# Control_and_Gauge.net
KiCad netlist of a schematic drawn in Altium Designer
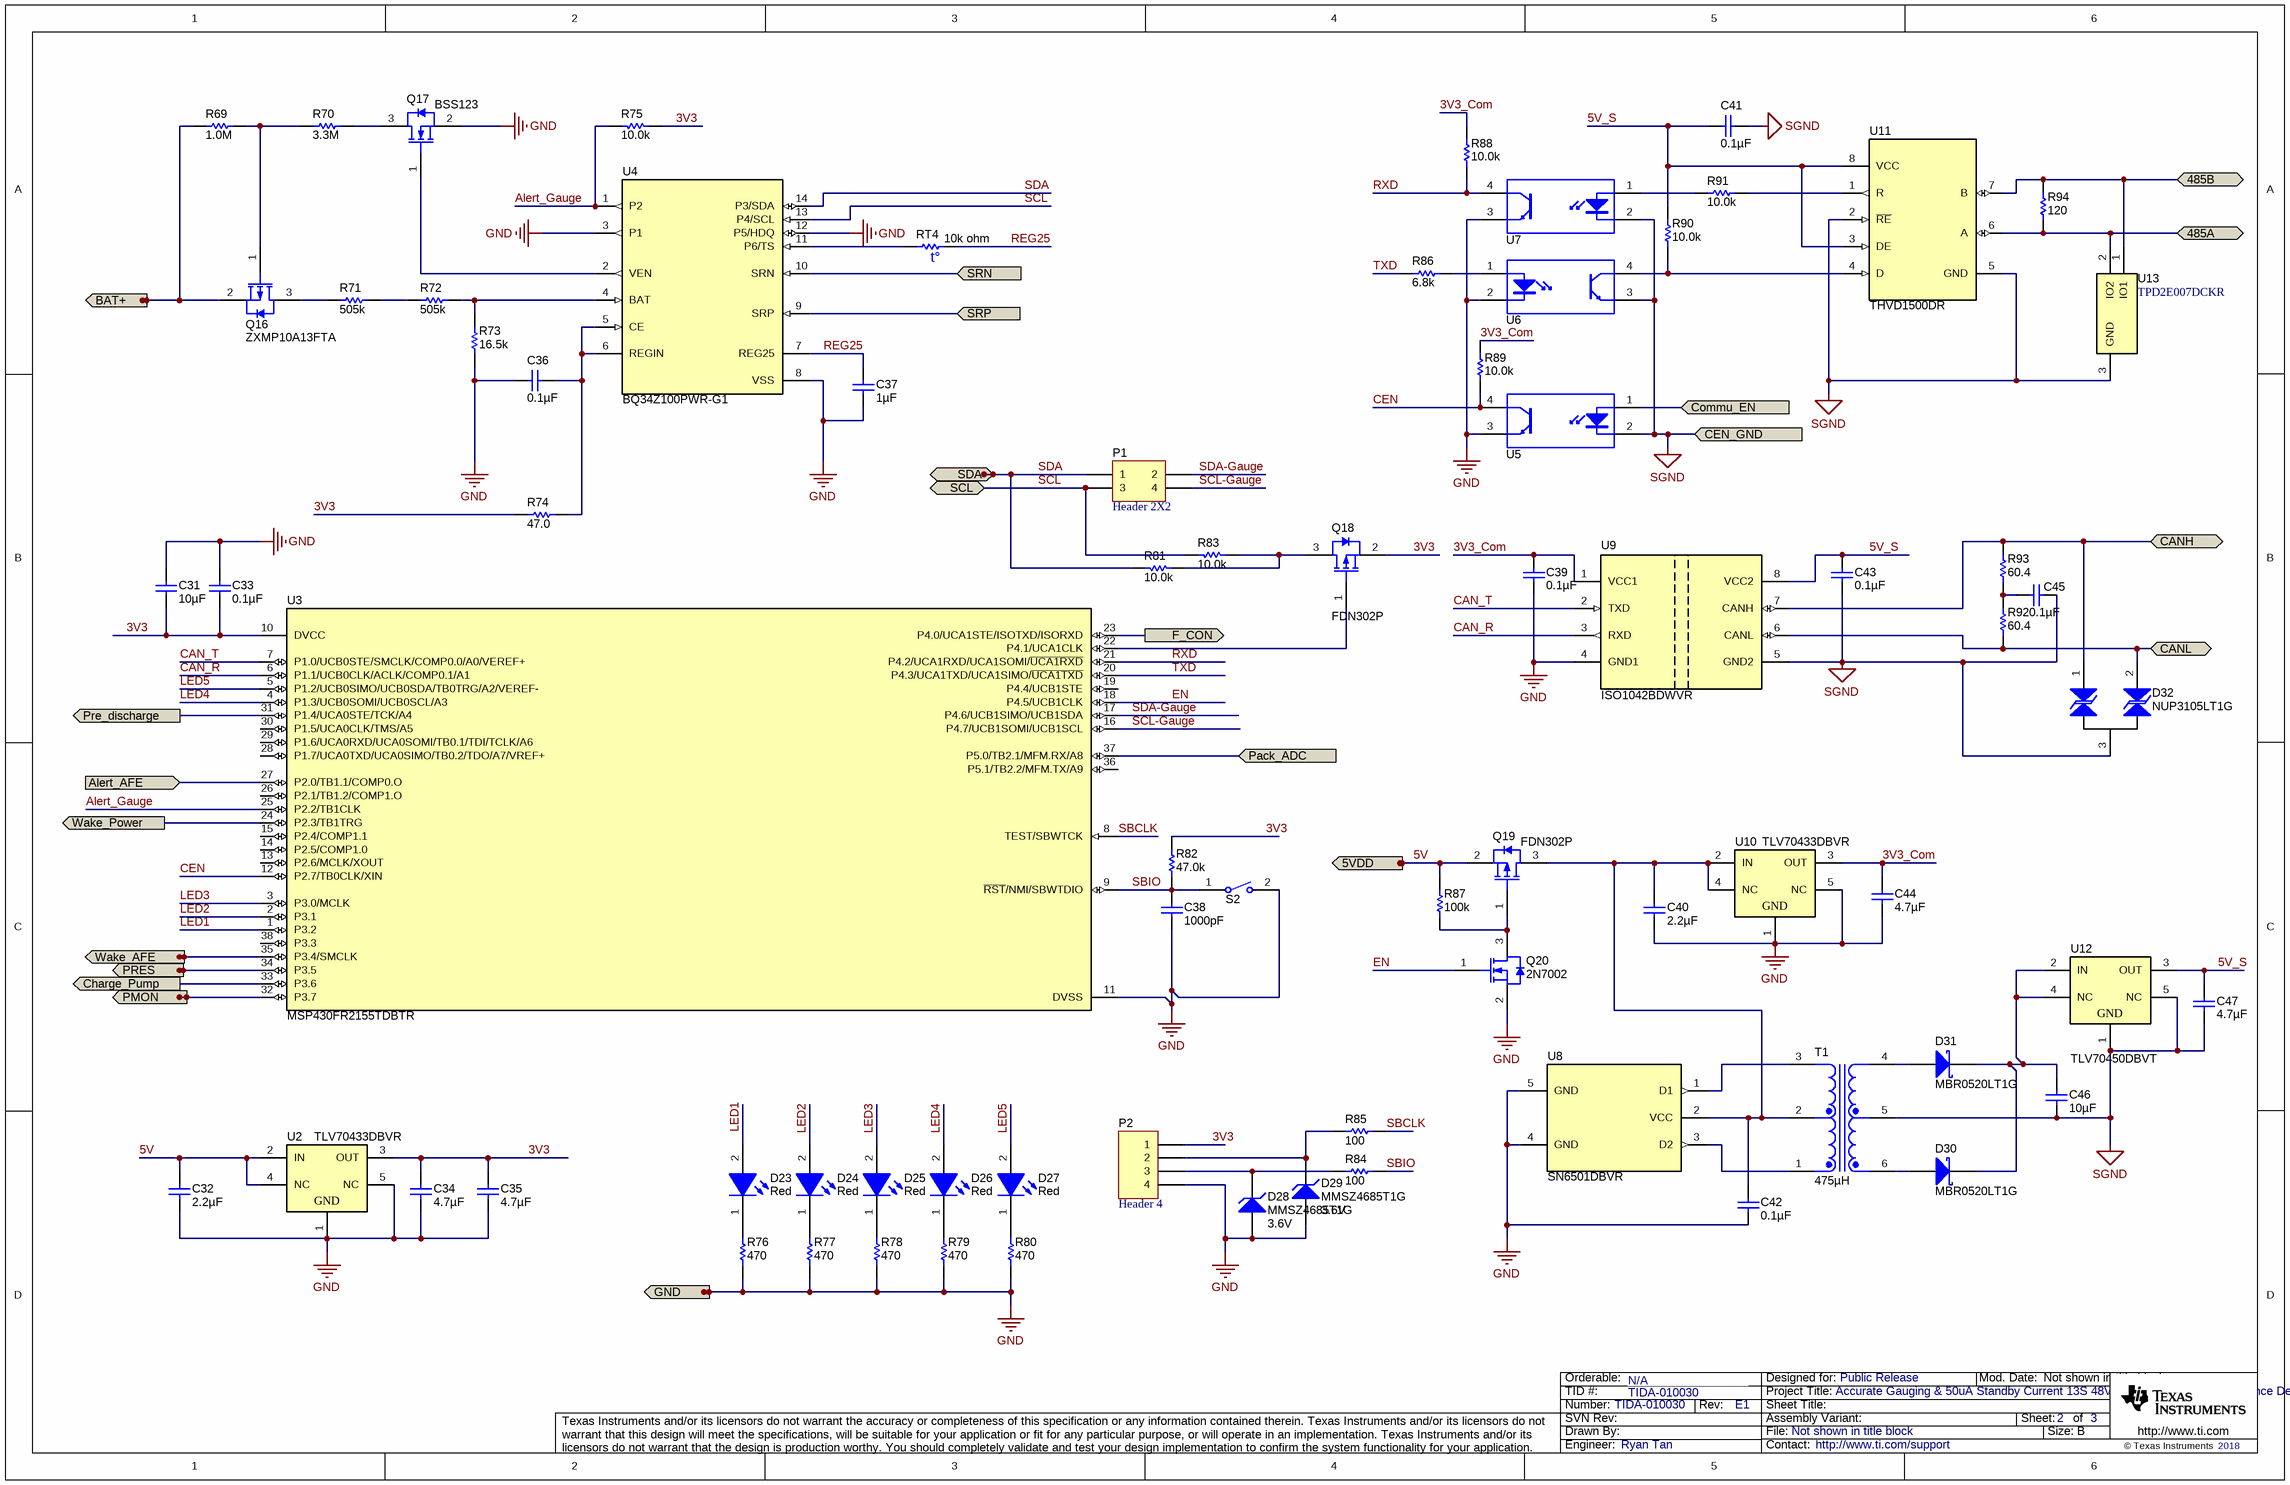
[diagram p0: Control and Gauge.SchDoc]

(export (version "E")
  (design (tool "Eeschema 10.0.6"))
  (components
    (comp (ref "C31")
      (value "CL21B106KOQNNNE")
      (footprint "0805_HV")
      (description "CAP, CERM, 10 µF, 16 V,+/- 10%, X7R, 0805")
      (fields
        (field (name "VALUEDISPLAYED") "10µF")
        (field (name "MANUFACTURER") "Samsung Electro-Mechanics")
        (field (name "PUBLISHER") "Texas Instruments")
      )
      (libsource (lib "Capacitor_Ceramic") (part "CL21B106KOQNNNE"))
    )
    (comp (ref "C32")
      (value "GRM188R71A225KE15D")
      (footprint "0603")
      (description "CAP, CERM, 2.2 µF, 10 V,+/- 10%, X7R, 0603")
      (fields
        (field (name "VALUEDISPLAYED") "2.2µF")
        (field (name "MANUFACTURER") "MuRata")
        (field (name "PUBLISHER") "Texas Instruments")
      )
      (libsource (lib "Capacitor_Ceramic") (part "GRM188R71A225KE15D"))
    )
    (comp (ref "C33")
      (value "GRM188R71C104KA01D")
      (footprint "0603")
      (description "CAP, CERM, 0.1 µF, 16 V,+/- 10%, X7R, 0603")
      (fields
        (field (name "VALUEDISPLAYED") "0.1µF")
        (field (name "MANUFACTURER") "MuRata")
        (field (name "PUBLISHER") "Texas Instruments")
      )
      (libsource (lib "Capacitor_Ceramic") (part "GRM188R71C104KA01D"))
    )
    (comp (ref "C34")
      (value "GRM188R61C475KAAJ")
      (footprint "0603")
      (description "CAP, CERM, 4.7 µF, 16 V,+/- 10%, X5R, 0603")
      (fields
        (field (name "VALUEDISPLAYED") "4.7µF")
        (field (name "MANUFACTURER") "MuRata")
        (field (name "PUBLISHER") "Texas Instruments")
      )
      (libsource (lib "Capacitor_Ceramic") (part "GRM188R61C475KAAJ"))
    )
    (comp (ref "C35")
      (value "GRM188R61C475KAAJ")
      (footprint "0603")
      (description "CAP, CERM, 4.7 µF, 16 V,+/- 10%, X5R, 0603")
      (fields
        (field (name "VALUEDISPLAYED") "4.7µF")
        (field (name "MANUFACTURER") "MuRata")
        (field (name "PUBLISHER") "Texas Instruments")
      )
      (libsource (lib "Capacitor_Ceramic") (part "GRM188R61C475KAAJ"))
    )
    (comp (ref "C36")
      (value "GRM188R71H104KA93D")
      (footprint "0603")
      (description "CAP, CERM, 0.1 µF, 50 V,+/- 10%, X7R, 0603")
      (fields
        (field (name "VALUEDISPLAYED") "0.1µF")
        (field (name "MANUFACTURER") "MuRata")
        (field (name "PUBLISHER") "Texas Instruments")
      )
      (libsource (lib "Capacitor_Ceramic") (part "GRM188R71H104KA93D"))
    )
    (comp (ref "C37")
      (value "GRM188R71C105KE15D")
      (footprint "0603")
      (description "CAP, CERM, 1 µF, 16 V,+/- 10%, X7R, 0603")
      (fields
        (field (name "VALUEDISPLAYED") "1µF")
        (field (name "MANUFACTURER") "MuRata")
        (field (name "PUBLISHER") "Texas Instruments")
      )
      (libsource (lib "Capacitor_Ceramic") (part "GRM188R71C105KE15D"))
    )
    (comp (ref "C38")
      (value "GRM1885C1H102JA01D")
      (footprint "0603S")
      (description "CAP, CERM, 1000 pF, 50 V,+/- 5%, C0G/NP0, 0603")
      (fields
        (field (name "VALUEDISPLAYED") "1000pF")
        (field (name "MANUFACTURER") "MuRata")
        (field (name "PUBLISHER") "Texas Instruments")
      )
      (libsource (lib "Capacitor_Ceramic") (part "GRM1885C1H102JA01D"))
    )
    (comp (ref "C39")
      (value "GRM188R71C104KA01D")
      (footprint "0603")
      (description "CAP, CERM, 0.1 µF, 16 V,+/- 10%, X7R, 0603")
      (fields
        (field (name "VALUEDISPLAYED") "0.1µF")
        (field (name "MANUFACTURER") "MuRata")
        (field (name "PUBLISHER") "Texas Instruments")
      )
      (libsource (lib "Capacitor_Ceramic") (part "GRM188R71C104KA01D"))
    )
    (comp (ref "C40")
      (value "GRM188R71A225KE15D")
      (footprint "0603")
      (description "CAP, CERM, 2.2 µF, 10 V,+/- 10%, X7R, 0603")
      (fields
        (field (name "VALUEDISPLAYED") "2.2µF")
        (field (name "MANUFACTURER") "MuRata")
        (field (name "PUBLISHER") "Texas Instruments")
      )
      (libsource (lib "Capacitor_Ceramic") (part "GRM188R71A225KE15D"))
    )
    (comp (ref "C41")
      (value "GRM188R71H104KA93D")
      (footprint "0603")
      (description "CAP, CERM, 0.1 µF, 50 V,+/- 10%, X7R, 0603")
      (fields
        (field (name "VALUEDISPLAYED") "0.1µF")
        (field (name "MANUFACTURER") "MuRata")
        (field (name "PUBLISHER") "Texas Instruments")
      )
      (libsource (lib "Capacitor_Ceramic") (part "GRM188R71H104KA93D"))
    )
    (comp (ref "C42")
      (value "GRM188R71C104KA01D")
      (footprint "0603")
      (description "CAP, CERM, 0.1 µF, 16 V,+/- 10%, X7R, 0603")
      (fields
        (field (name "VALUEDISPLAYED") "0.1µF")
        (field (name "MANUFACTURER") "MuRata")
        (field (name "PUBLISHER") "Texas Instruments")
      )
      (libsource (lib "Capacitor_Ceramic") (part "GRM188R71C104KA01D"))
    )
    (comp (ref "C43")
      (value "GRM188R71H104KA93D")
      (footprint "0603")
      (description "CAP, CERM, 0.1 µF, 50 V,+/- 10%, X7R, 0603")
      (fields
        (field (name "VALUEDISPLAYED") "0.1µF")
        (field (name "MANUFACTURER") "MuRata")
        (field (name "PUBLISHER") "Texas Instruments")
      )
      (libsource (lib "Capacitor_Ceramic") (part "GRM188R71H104KA93D"))
    )
    (comp (ref "C44")
      (value "GRM188R61C475KAAJ")
      (footprint "0603")
      (description "CAP, CERM, 4.7 µF, 16 V,+/- 10%, X5R, 0603")
      (fields
        (field (name "VALUEDISPLAYED") "4.7µF")
        (field (name "MANUFACTURER") "MuRata")
        (field (name "PUBLISHER") "Texas Instruments")
      )
      (libsource (lib "Capacitor_Ceramic") (part "GRM188R61C475KAAJ"))
    )
    (comp (ref "C45")
      (value "GRM188R71H104KA93D")
      (footprint "0603S")
      (description "CAP, CERM, 0.1 µF, 50 V,+/- 10%, X7R, 0603")
      (fields
        (field (name "VALUEDISPLAYED") "0.1µF")
        (field (name "MANUFACTURER") "MuRata")
        (field (name "PUBLISHER") "Texas Instruments")
      )
      (libsource (lib "Capacitor_Ceramic") (part "GRM188R71H104KA93D"))
    )
    (comp (ref "C46")
      (value "CL21B106KOQNNNE")
      (footprint "0805_HV")
      (description "CAP, CERM, 10 µF, 16 V,+/- 10%, X7R, 0805")
      (fields
        (field (name "VALUEDISPLAYED") "10µF")
        (field (name "MANUFACTURER") "Samsung Electro-Mechanics")
        (field (name "PUBLISHER") "Texas Instruments")
      )
      (libsource (lib "Capacitor_Ceramic") (part "CL21B106KOQNNNE"))
    )
    (comp (ref "C47")
      (value "GRM188R61C475KAAJ")
      (footprint "0603")
      (description "CAP, CERM, 4.7 µF, 16 V,+/- 10%, X5R, 0603")
      (fields
        (field (name "VALUEDISPLAYED") "4.7µF")
        (field (name "MANUFACTURER") "MuRata")
        (field (name "PUBLISHER") "Texas Instruments")
      )
      (libsource (lib "Capacitor_Ceramic") (part "GRM188R61C475KAAJ"))
    )
    (comp (ref "D23")
      (value "Red")
      (footprint "WL-SMCW_RED")
      (description "LED, Red, SMD")
      (fields
        (field (name "MANUFACTURER") "Wurth Elektronik")
        (field (name "PARTNUMBER") "150060RS75000")
        (field (name "PUBLISHER") "Texas Instruments")
      )
      (libsource (lib "LED") (part "150060RS75000"))
    )
    (comp (ref "D24")
      (value "Red")
      (footprint "WL-SMCW_RED")
      (description "LED, Red, SMD")
      (fields
        (field (name "MANUFACTURER") "Wurth Elektronik")
        (field (name "PARTNUMBER") "150060RS75000")
        (field (name "PUBLISHER") "Texas Instruments")
      )
      (libsource (lib "LED") (part "150060RS75000"))
    )
    (comp (ref "D25")
      (value "Red")
      (footprint "WL-SMCW_RED")
      (description "LED, Red, SMD")
      (fields
        (field (name "MANUFACTURER") "Wurth Elektronik")
        (field (name "PARTNUMBER") "150060RS75000")
        (field (name "PUBLISHER") "Texas Instruments")
      )
      (libsource (lib "LED") (part "150060RS75000"))
    )
    (comp (ref "D26")
      (value "Red")
      (footprint "WL-SMCW_RED")
      (description "LED, Red, SMD")
      (fields
        (field (name "MANUFACTURER") "Wurth Elektronik")
        (field (name "PARTNUMBER") "150060RS75000")
        (field (name "PUBLISHER") "Texas Instruments")
      )
      (libsource (lib "LED") (part "150060RS75000"))
    )
    (comp (ref "D27")
      (value "Red")
      (footprint "WL-SMCW_RED")
      (description "LED, Red, SMD")
      (fields
        (field (name "MANUFACTURER") "Wurth Elektronik")
        (field (name "PARTNUMBER") "150060RS75000")
        (field (name "PUBLISHER") "Texas Instruments")
      )
      (libsource (lib "LED") (part "150060RS75000"))
    )
    (comp (ref "D28")
      (value "MMSZ4685T1G")
      (footprint "SOD-123")
      (description "Diode, Zener, 3.6 V, 500 mW, SOD-123")
      (fields
        (field (name "ALTIUM_VALUE") "3.6V")
        (field (name "MANUFACTURER") "ON Semiconductor")
        (field (name "SYMBOLCREATOR") "a0412235")
        (field (name "PUBLISHER") "Texas Instruments")
      )
      (libsource (lib "ZenerDiodes") (part "MMSZ4685T1G"))
    )
    (comp (ref "D29")
      (value "MMSZ4685T1G")
      (footprint "SOD-123")
      (description "Diode, Zener, 3.6 V, 500 mW, SOD-123")
      (fields
        (field (name "ALTIUM_VALUE") "3.6V")
        (field (name "MANUFACTURER") "ON Semiconductor")
        (field (name "SYMBOLCREATOR") "a0412235")
        (field (name "PUBLISHER") "Texas Instruments")
      )
      (libsource (lib "ZenerDiodes") (part "MMSZ4685T1G"))
    )
    (comp (ref "D30")
      (value "MBR0520LT1G")
      (footprint "SOD-123")
      (description "Diode, Schottky, 20 V, 0.5 A, SOD-123")
      (fields (field (name "MANUFACTURER") "ON Semiconductor") (field (name "PUBLISHER") "Texas Instruments"))
      (libsource (lib "Diode") (part "MBR0520LT1G"))
    )
    (comp (ref "D31")
      (value "MBR0520LT1G")
      (footprint "SOD-123")
      (description "Diode, Schottky, 20 V, 0.5 A, SOD-123")
      (fields (field (name "MANUFACTURER") "ON Semiconductor") (field (name "PUBLISHER") "Texas Instruments"))
      (libsource (lib "Diode") (part "MBR0520LT1G"))
    )
    (comp (ref "D32")
      (value "NUP3105LT1G")
      (footprint "SOT-23")
      (description "Diode, TVS, Bi, 24 V, SOT-23")
      (fields
        (field (name "MANUFACTURER") "ON Semiconductor")
        (field (name "SYMBOLCREATOR") "a0411947")
        (field (name "PUBLISHER") "Texas Instruments")
      )
      (libsource (lib "ZenerDiodes") (part "NUP2105LT1G"))
    )
    (comp (ref "P1")
      (value "Header 2X2")
      (footprint "HDR2X2")
      (description "Header, 2-Pin, Dual row")
      (fields (field (name "PUBLISHER") "Altium Limited"))
      (libsource (lib "Miscellaneous Connectors") (part "Header 2X2"))
    )
    (comp (ref "P2")
      (value "Header 4")
      (footprint "HDR1X4")
      (description "Header, 4-Pin")
      (fields (field (name "PUBLISHER") "Altium Limited"))
      (libsource (lib "Miscellaneous Connectors") (part "Header 4"))
    )
    (comp (ref "Q16")
      (value "ZXMP10A13FTA")
      (footprint "SOT-23")
      (description "MOSFET, P-CH, -100 V, -0.6 A, SOT-23")
      (fields (field (name "MANUFACTURER") "Diodes Inc.") (field (name "PUBLISHER") "Texas Instruments"))
      (libsource (lib "FETs") (part "ZXMP10A13FTA"))
    )
    (comp (ref "Q17")
      (value "BSS123")
      (footprint "SOT-23")
      (description "MOSFET, N-CH, 100 V, 0.17 A, SOT-23")
      (fields
        (field (name "MANUFACTURER") "Fairchild Semiconductor")
        (field (name "PUBLISHER") "Texas Instruments")
      )
      (libsource (lib "FETs") (part "BSS123"))
    )
    (comp (ref "Q18")
      (value "FDN302P")
      (footprint "SOT-23")
      (description "MOSFET, P-CH, -20 V, -2.4 A, SOT-23")
      (fields
        (field (name "MANUFACTURER") "Fairchild Semiconductor")
        (field (name "PUBLISHER") "Texas Instruments")
      )
      (libsource (lib "FETs") (part "FDN302P"))
    )
    (comp (ref "Q19")
      (value "FDN302P")
      (footprint "SOT-23")
      (description "MOSFET, P-CH, -20 V, -2.4 A, SOT-23")
      (fields
        (field (name "MANUFACTURER") "Fairchild Semiconductor")
        (field (name "PUBLISHER") "Texas Instruments")
      )
      (libsource (lib "FETs") (part "FDN302P"))
    )
    (comp (ref "Q20")
      (value "2N7002")
      (footprint "SOT-23")
      (description "MOSFET, N-CH, 60 V, 115 A, SOT-23")
      (fields
        (field (name "MANUFACTURER") "Fairchild Semiconductor")
        (field (name "PUBLISHER") "Texas Instruments")
      )
      (libsource (lib "FETs") (part "2N7002"))
    )
    (comp (ref "R69")
      (value "CRCW06031M00JNEA")
      (footprint "0603")
      (description "RES, 1.0 M, 5%, 0.1 W, 0603")
      (fields
        (field (name "VALUEDISPLAYED") "1.0M")
        (field (name "MANUFACTURER") "Vishay-Dale")
        (field (name "PUBLISHER") "Texas Instruments")
      )
      (libsource (lib "Resistor_0603") (part "CRCW06031M00JNEA"))
    )
    (comp (ref "R70")
      (value "CRCW06033M30JNEA")
      (footprint "0603")
      (description "RES, 3.3 M, 5%, 0.1 W, 0603")
      (fields
        (field (name "VALUEDISPLAYED") "3.3M")
        (field (name "MANUFACTURER") "Vishay-Dale")
        (field (name "PUBLISHER") "Texas Instruments")
      )
      (libsource (lib "Resistor_0603") (part "CRCW06033M30JNEA"))
    )
    (comp (ref "R71")
      (value "RT0603BRD07505KL")
      (footprint "0603")
      (description "RES, 505 k, 0.1%, 0.1 W, 0603")
      (fields
        (field (name "VALUEDISPLAYED") "505k")
        (field (name "MANUFACTURER") "Yageo America")
        (field (name "PUBLISHER") "Texas Instruments")
      )
      (libsource (lib "Resistor_0603") (part "RT0603BRD07505KL"))
    )
    (comp (ref "R72")
      (value "RT0603BRD07505KL")
      (footprint "0603")
      (description "RES, 505 k, 0.1%, 0.1 W, 0603")
      (fields
        (field (name "VALUEDISPLAYED") "505k")
        (field (name "MANUFACTURER") "Yageo America")
        (field (name "PUBLISHER") "Texas Instruments")
      )
      (libsource (lib "Resistor_0603") (part "RT0603BRD07505KL"))
    )
    (comp (ref "R73")
      (value "RT0603BRD0716K5L")
      (footprint "0603")
      (description "RES, 16.5 k, 0.1%, 0.1 W, 0603")
      (fields
        (field (name "VALUEDISPLAYED") "16.5k")
        (field (name "MANUFACTURER") "Yageo America")
        (field (name "PUBLISHER") "Texas Instruments")
      )
      (libsource (lib "Resistor_0603") (part "RT0603BRD0716K5L"))
    )
    (comp (ref "R74")
      (value "RC0603FR-0747RL")
      (footprint "0603")
      (description "RES, 47.0, 1%, 0.1 W, 0603")
      (fields
        (field (name "VALUEDISPLAYED") "47.0")
        (field (name "MANUFACTURER") "Yageo America")
        (field (name "PUBLISHER") "Texas Instruments")
      )
      (libsource (lib "Resistor_0603") (part "RC0603FR-0747RL"))
    )
    (comp (ref "R75")
      (value "CRCW060310K0FKEA")
      (footprint "0603")
      (description "RES, 10.0 k, 1%, 0.1 W, 0603")
      (fields
        (field (name "VALUEDISPLAYED") "10.0k")
        (field (name "MANUFACTURER") "Vishay-Dale")
        (field (name "PUBLISHER") "Texas Instruments")
      )
      (libsource (lib "Resistor_0603") (part "CRCW060310K0FKEA"))
    )
    (comp (ref "R76")
      (value "RC0603FR-07470RL")
      (footprint "0603")
      (description "RES, 470, 1%, 0.1 W, 0603")
      (fields
        (field (name "VALUEDISPLAYED") "470")
        (field (name "MANUFACTURER") "Yageo America")
        (field (name "PUBLISHER") "Texas Instruments")
      )
      (libsource (lib "Resistor_0603") (part "RC0603FR-07470RL"))
    )
    (comp (ref "R77")
      (value "RC0603FR-07470RL")
      (footprint "0603")
      (description "RES, 470, 1%, 0.1 W, 0603")
      (fields
        (field (name "VALUEDISPLAYED") "470")
        (field (name "MANUFACTURER") "Yageo America")
        (field (name "PUBLISHER") "Texas Instruments")
      )
      (libsource (lib "Resistor_0603") (part "RC0603FR-07470RL"))
    )
    (comp (ref "R78")
      (value "RC0603FR-07470RL")
      (footprint "0603")
      (description "RES, 470, 1%, 0.1 W, 0603")
      (fields
        (field (name "VALUEDISPLAYED") "470")
        (field (name "MANUFACTURER") "Yageo America")
        (field (name "PUBLISHER") "Texas Instruments")
      )
      (libsource (lib "Resistor_0603") (part "RC0603FR-07470RL"))
    )
    (comp (ref "R79")
      (value "RC0603FR-07470RL")
      (footprint "0603")
      (description "RES, 470, 1%, 0.1 W, 0603")
      (fields
        (field (name "VALUEDISPLAYED") "470")
        (field (name "MANUFACTURER") "Yageo America")
        (field (name "PUBLISHER") "Texas Instruments")
      )
      (libsource (lib "Resistor_0603") (part "RC0603FR-07470RL"))
    )
    (comp (ref "R80")
      (value "RC0603FR-07470RL")
      (footprint "0603")
      (description "RES, 470, 1%, 0.1 W, 0603")
      (fields
        (field (name "VALUEDISPLAYED") "470")
        (field (name "MANUFACTURER") "Yageo America")
        (field (name "PUBLISHER") "Texas Instruments")
      )
      (libsource (lib "Resistor_0603") (part "RC0603FR-07470RL"))
    )
    (comp (ref "R81")
      (value "CRCW060310K0FKEA")
      (footprint "0603")
      (description "RES, 10.0 k, 1%, 0.1 W, 0603")
      (fields
        (field (name "VALUEDISPLAYED") "10.0k")
        (field (name "MANUFACTURER") "Vishay-Dale")
        (field (name "PUBLISHER") "Texas Instruments")
      )
      (libsource (lib "Resistor_0603") (part "CRCW060310K0FKEA"))
    )
    (comp (ref "R82")
      (value "RC0603FR-0747KL")
      (footprint "0603")
      (description "RES, 47.0 k, 1%, 0.1 W, 0603")
      (fields
        (field (name "VALUEDISPLAYED") "47.0k")
        (field (name "MANUFACTURER") "Yageo America")
        (field (name "PUBLISHER") "Texas Instruments")
      )
      (libsource (lib "Resistor_0603") (part "RC0603FR-0747KL"))
    )
    (comp (ref "R83")
      (value "CRCW060310K0FKEA")
      (footprint "0603")
      (description "RES, 10.0 k, 1%, 0.1 W, 0603")
      (fields
        (field (name "VALUEDISPLAYED") "10.0k")
        (field (name "MANUFACTURER") "Vishay-Dale")
        (field (name "PUBLISHER") "Texas Instruments")
      )
      (libsource (lib "Resistor_0603") (part "CRCW060310K0FKEA"))
    )
    (comp (ref "R84")
      (value "CRCW0603100RFKEA")
      (footprint "0603")
      (description "RES, 100, 1%, 0.1 W, 0603")
      (fields
        (field (name "VALUEDISPLAYED") "100")
        (field (name "MANUFACTURER") "Vishay-Dale")
        (field (name "PUBLISHER") "Texas Instruments")
      )
      (libsource (lib "Resistor_0603") (part "CRCW0603100RFKEA"))
    )
    (comp (ref "R85")
      (value "CRCW0603100RFKEA")
      (footprint "0603")
      (description "RES, 100, 1%, 0.1 W, 0603")
      (fields
        (field (name "VALUEDISPLAYED") "100")
        (field (name "MANUFACTURER") "Vishay-Dale")
        (field (name "PUBLISHER") "Texas Instruments")
      )
      (libsource (lib "Resistor_0603") (part "CRCW0603100RFKEA"))
    )
    (comp (ref "R86")
      (value "CRCW06036K80JNEA")
      (footprint "0603")
      (description "RES, 6.8 k, 5%, 0.1 W, 0603")
      (fields
        (field (name "VALUEDISPLAYED") "6.8k")
        (field (name "MANUFACTURER") "Vishay-Dale")
        (field (name "PUBLISHER") "Texas Instruments")
      )
      (libsource (lib "Resistor_0603") (part "CRCW06036K80JNEA"))
    )
    (comp (ref "R87")
      (value "CRCW0603100KFKEA")
      (footprint "0603")
      (description "RES, 100 k, 1%, 0.1 W, 0603")
      (fields
        (field (name "VALUEDISPLAYED") "100k")
        (field (name "MANUFACTURER") "Vishay-Dale")
        (field (name "PUBLISHER") "Texas Instruments")
      )
      (libsource (lib "Resistor_0603") (part "CRCW0603100KFKEA"))
    )
    (comp (ref "R88")
      (value "CRCW060310K0FKEA")
      (footprint "0603")
      (description "RES, 10.0 k, 1%, 0.1 W, 0603")
      (fields
        (field (name "VALUEDISPLAYED") "10.0k")
        (field (name "MANUFACTURER") "Vishay-Dale")
        (field (name "PUBLISHER") "Texas Instruments")
      )
      (libsource (lib "Resistor_0603") (part "CRCW060310K0FKEA"))
    )
    (comp (ref "R89")
      (value "CRCW060310K0FKEA")
      (footprint "0603")
      (description "RES, 10.0 k, 1%, 0.1 W, 0603")
      (fields
        (field (name "VALUEDISPLAYED") "10.0k")
        (field (name "MANUFACTURER") "Vishay-Dale")
        (field (name "PUBLISHER") "Texas Instruments")
      )
      (libsource (lib "Resistor_0603") (part "CRCW060310K0FKEA"))
    )
    (comp (ref "R90")
      (value "CRCW060310K0FKEA")
      (footprint "0603")
      (description "RES, 10.0 k, 1%, 0.1 W, 0603")
      (fields
        (field (name "VALUEDISPLAYED") "10.0k")
        (field (name "MANUFACTURER") "Vishay-Dale")
        (field (name "PUBLISHER") "Texas Instruments")
      )
      (libsource (lib "Resistor_0603") (part "CRCW060310K0FKEA"))
    )
    (comp (ref "R91")
      (value "CRCW060310K0FKEA")
      (footprint "0603S")
      (description "RES, 10.0 k, 1%, 0.1 W, 0603")
      (fields
        (field (name "VALUEDISPLAYED") "10.0k")
        (field (name "MANUFACTURER") "Vishay-Dale")
        (field (name "PUBLISHER") "Texas Instruments")
      )
      (libsource (lib "Resistor_0603") (part "CRCW060310K0FKEA"))
    )
    (comp (ref "R92")
      (value "RC0603FR-0760R4L")
      (footprint "0603S")
      (description "RES, 60.4, 1%, 0.1 W, 0603")
      (fields
        (field (name "VALUEDISPLAYED") "60.4")
        (field (name "MANUFACTURER") "Yageo America")
        (field (name "PUBLISHER") "Texas Instruments")
      )
      (libsource (lib "Resistor_0603") (part "RC0603FR-0760R4L"))
    )
    (comp (ref "R93")
      (value "RC0603FR-0760R4L")
      (footprint "0603S")
      (description "RES, 60.4, 1%, 0.1 W, 0603")
      (fields
        (field (name "VALUEDISPLAYED") "60.4")
        (field (name "MANUFACTURER") "Yageo America")
        (field (name "PUBLISHER") "Texas Instruments")
      )
      (libsource (lib "Resistor_0603") (part "RC0603FR-0760R4L"))
    )
    (comp (ref "R94")
      (value "RC0603FR-07120RL")
      (footprint "0603")
      (description "RES, 120, 1%, 0.1 W, 0603")
      (fields
        (field (name "VALUEDISPLAYED") "120")
        (field (name "MANUFACTURER") "Yageo America")
        (field (name "PUBLISHER") "Texas Instruments")
      )
      (libsource (lib "Resistor_0603") (part "RC0603FR-07120RL"))
    )
    (comp (ref "RT4")
      (value "10k ohm")
      (footprint "NTCALUG03")
      (description "Thermistor NTC, 10k ohm, 2%, NTC Thermistor, Mini Lug Sensor, Pitch 1.5mm")
      (fields
        (field (name "PARTNUMBER") "NTCALUG03A103G")
        (field (name "MANUFACTURER") "Vishay-Bccomponents")
        (field (name "PUBLISHER") "Texas Instruments")
      )
      (libsource (lib "ThermistorNTC") (part "NTCALUG03A103G"))
    )
    (comp (ref "S2")
      (value "RS-032G05A3-SM RT")
      (footprint "SW_RS-032G05A3-SM")
      (description "Switch, Tactile, SPST-NO, 0.05A, 12V, SMD")
      (fields
        (field (name "MANUFACTURER") "C&K Components")
        (field (name "SYMBOLCREATOR") "a0799628")
        (field (name "PUBLISHER") "Texas Instruments")
      )
      (libsource (lib "Switches") (part "RS-032G05A3-SM RT"))
    )
    (comp (ref "T1")
      (value "760390012")
      (footprint "Wurth_760390012")
      (description "Transformer, 475 uH, SMT")
      (fields
        (field (name "VALUEDISPLAYED") "475µH")
        (field (name "MANUFACTURER") "Wurth Elektronik")
        (field (name "SYMBOLCREATOR") "Altium")
        (field (name "PUBLISHER") "Texas Instruments")
      )
      (libsource (lib "Transformers") (part "760390012"))
    )
    (comp (ref "U2")
      (value "TLV70433DBVR")
      (footprint "DBV0005A_N")
      (fields
        (field (name "MANUFACTURER") "Texas Instruments")
        (field (name "ALTERNATE PARTNUMBER") "Equivalent")
      )
      (libsource (lib "TI Power Management Linear Regulator Single Channel LDO (0-350mA)") (part "TLV70433DBVR"))
    )
    (comp (ref "U3")
      (value "MSP430FR2155TDBTR")
      (footprint "DBT0038A_N")
      (description "24MHz 105C ULP Microcontroller With 32 KB FRAM, 4 KB SRAM, 44 IO, 12-bit ADC, DBT0038A (TSSOP-38)")
      (fields
        (field (name "PARTNUMBER") "MSP430FR2155TDBTR")
        (field (name "MANUFACTURER") "Texas Instruments")
        (field (name "ALTERNATE PARTNUMBER") "MSP430FR2155TDBT")
      )
      (libsource (lib "Altium Vault - TI") (part "MSP430FR215xTDBT"))
    )
    (comp (ref "U4")
      (value "BQ34Z100PWR-G1")
      (footprint "PW0014A_N")
      (description "Multi-Chemistry Impedance Track Standalone Fuel Gauge")
      (fields
        (field (name "ALTERNATE PARTNUMBER") "BQ34Z100PW-G1")
        (field (name "MANUFACTURER") "Texas Instruments")
        (field (name "PARTNUMBER") "BQ34Z100PWR-G1")
      )
      (libsource (lib "Altium Vault - TI") (part "BQ34Z100"))
    )
    (comp (ref "U5")
      (value "TLP293(GB-TPL,E")
      (footprint "SO4")
      (description "Optocoupler, 3.75 kV, 100-600% CTR, SMT")
      (fields (field (name "MANUFACTURER") "Toshiba") (field (name "PUBLISHER") "Texas Instruments"))
      (libsource (lib "OptoCouplers") (part "TLP293(GB-TPL,E"))
    )
    (comp (ref "U6")
      (value "TLP293(GB-TPL,E")
      (footprint "SO4")
      (description "Optocoupler, 3.75 kV, 100-600% CTR, SMT")
      (fields (field (name "MANUFACTURER") "Toshiba") (field (name "PUBLISHER") "Texas Instruments"))
      (libsource (lib "OptoCouplers") (part "TLP293(GB-TPL,E"))
    )
    (comp (ref "U7")
      (value "TLP293(GB-TPL,E")
      (footprint "SO4")
      (description "Optocoupler, 3.75 kV, 100-600% CTR, SMT")
      (fields (field (name "MANUFACTURER") "Toshiba") (field (name "PUBLISHER") "Texas Instruments"))
      (libsource (lib "OptoCouplers") (part "TLP293(GB-TPL,E"))
    )
    (comp (ref "U8")
      (value "SN6501DBVR")
      (footprint "DBV0005A_N")
      (description "Low-Noise 350 mA, 410 kHz Transformer Driver, DBV0005A (SOT-23-5)")
      (fields
        (field (name "ALTERNATE PARTNUMBER") "SN6501DBVT")
        (field (name "MANUFACTURER") "Texas Instruments")
        (field (name "PARTNUMBER") "SN6501DBVR")
        (field (name "PUBLISHER") "Texas Instruments")
      )
      (libsource (lib "Altium Vault - TI") (part "SN6501"))
    )
    (comp (ref "U9")
      (value "ISO1042BDWVR")
      (footprint "DWV0008A")
      (description "Reinforced Isolated CAN XCVRs with 70V Protection Voltage and CAN FD, DWV0008A (SOIC-8)")
      (fields
        (field (name "ALTERNATE PARTNUMBER") "ISO1042BDWV")
        (field (name "MANUFACTURER") "Texas Instruments")
        (field (name "PARTNUMBER") "ISO1042BDWVR")
      )
      (libsource (lib "Altium Vault - TI") (part "CMP-0077952-1"))
    )
    (comp (ref "U10")
      (value "TLV70433DBVR")
      (footprint "DBV0005A_N")
      (fields
        (field (name "MANUFACTURER") "Texas Instruments")
        (field (name "ALTERNATE PARTNUMBER") "Equivalent")
      )
      (libsource (lib "TI Power Management Linear Regulator Single Channel LDO (0-350mA)") (part "TLV70433DBVR"))
    )
    (comp (ref "U11")
      (value "THVD1500DR")
      (footprint "D0008A_N")
      (description "250 kbps RS-485 Transceivers With +/-12-kV IEC ESD Protection, D0008A (SOIC-8)")
      (fields
        (field (name "PARTNUMBER") "THVD1500DR")
        (field (name "MANUFACTURER") "Texas Instruments")
        (field (name "ALTERNATE PARTNUMBER") "THVD1500D")
        (field (name "PUBLISHER") "Texas Instruments")
      )
      (libsource (lib "Altium Vault - TI") (part "THVD1500"))
    )
    (comp (ref "U12")
      (value "TLV70450DBVT")
      (footprint "DBV0005A_N")
      (fields
        (field (name "MANUFACTURER") "Texas Instruments")
        (field (name "ALTERNATE PARTNUMBER") "Equivalent")
      )
      (libsource (lib "TI Power Management Linear Regulator Single Channel LDO (0-350mA)") (part "TLV70450DBVT"))
    )
    (comp (ref "U13")
      (value "TPD2E007DCKR")
      (footprint "DCK0003A_N")
      (fields
        (field (name "MANUFACTURER") "Texas Instruments")
        (field (name "ALTERNATE PARTNUMBER") "Equivalent")
      )
      (libsource (lib "TI Interface ESD EMI Protection") (part "TPD2E007DCKR"))
    )
  )
  (nets
    (net (code "1") (name "/3V3") (class "Default")
      (node (ref "C31") (pin "2") (pinfunction "2_2") (pintype "passive"))
      (node (ref "C33") (pin "2") (pinfunction "2_2") (pintype "passive"))
      (node (ref "C34") (pin "1") (pinfunction "1_1") (pintype "passive"))
      (node (ref "C35") (pin "1") (pinfunction "1_1") (pintype "passive"))
      (node (ref "P2") (pin "1") (pinfunction "1_1") (pintype "passive"))
      (node (ref "Q18") (pin "2") (pinfunction "S_2") (pintype "passive"))
      (node (ref "R74") (pin "1") (pinfunction "1_1") (pintype "passive"))
      (node (ref "R75") (pin "1") (pinfunction "1_1") (pintype "passive"))
      (node (ref "R82") (pin "2") (pinfunction "2_2") (pintype "passive"))
      (node (ref "U2") (pin "3") (pinfunction "OUT_3") (pintype "power_in"))
      (node (ref "U3") (pin "10") (pinfunction "DVCC_10") (pintype "power_in"))
    )
    (net (code "2") (name "/3V3_Com") (class "Default")
      (node (ref "C39") (pin "2") (pinfunction "2_2") (pintype "passive"))
      (node (ref "C44") (pin "1") (pinfunction "1_1") (pintype "passive"))
      (node (ref "R88") (pin "2") (pinfunction "2_2") (pintype "passive"))
      (node (ref "R89") (pin "2") (pinfunction "2_2") (pintype "passive"))
      (node (ref "U10") (pin "3") (pinfunction "OUT_3") (pintype "power_in"))
      (node (ref "U9") (pin "1") (pinfunction "VCC1_1") (pintype "power_in"))
    )
    (net (code "3") (name "/5V") (class "Default")
      (node (ref "C32") (pin "1") (pinfunction "1_1") (pintype "passive"))
      (node (ref "Q19") (pin "2") (pinfunction "S_2") (pintype "passive"))
      (node (ref "R87") (pin "1") (pinfunction "1_1") (pintype "passive"))
      (node (ref "U2") (pin "2") (pinfunction "IN_2") (pintype "power_in"))
      (node (ref "U2") (pin "4") (pinfunction "NC_4") (pintype "passive"))
    )
    (net (code "4") (name "/5V_S") (class "Default")
      (node (ref "C41") (pin "1") (pinfunction "1_1") (pintype "passive"))
      (node (ref "C43") (pin "1") (pinfunction "1_1") (pintype "passive"))
      (node (ref "C47") (pin "1") (pinfunction "1_1") (pintype "passive"))
      (node (ref "R90") (pin "2") (pinfunction "2_2") (pintype "passive"))
      (node (ref "U11") (pin "3") (pinfunction "DE_3") (pintype "input"))
      (node (ref "U11") (pin "8") (pinfunction "VCC_8") (pintype "passive"))
      (node (ref "U12") (pin "3") (pinfunction "OUT_3") (pintype "power_in"))
      (node (ref "U9") (pin "8") (pinfunction "VCC2_8") (pintype "power_in"))
    )
    (net (code "5") (name "/485A") (class "Default")
      (node (ref "R94") (pin "2") (pinfunction "2_2") (pintype "passive"))
      (node (ref "U11") (pin "6") (pinfunction "A_6") (pintype "bidirectional"))
      (node (ref "U13") (pin "2") (pinfunction "IO2_2") (pintype "passive"))
    )
    (net (code "6") (name "/485B") (class "Default")
      (node (ref "R94") (pin "1") (pinfunction "1_1") (pintype "passive"))
      (node (ref "U11") (pin "7") (pinfunction "B_7") (pintype "bidirectional"))
      (node (ref "U13") (pin "1") (pinfunction "IO1_1") (pintype "passive"))
    )
    (net (code "7") (name "/Alert_AFE") (class "Default")
      (node (ref "U3") (pin "27") (pinfunction "P2.0/TB1.1/COMP0.O_27") (pintype "bidirectional"))
    )
    (net (code "8") (name "/Alert_Gauge") (class "Default")
      (node (ref "R75") (pin "2") (pinfunction "2_2") (pintype "passive"))
      (node (ref "U3") (pin "25") (pinfunction "P2.2/TB1CLK_25") (pintype "bidirectional"))
      (node (ref "U4") (pin "1") (pinfunction "P2_1") (pintype "output"))
    )
    (net (code "9") (name "/BAT+") (class "Default")
      (node (ref "Q16") (pin "2") (pinfunction "S_2") (pintype "passive"))
      (node (ref "R69") (pin "1") (pinfunction "1_1") (pintype "passive"))
    )
    (net (code "10") (name "/CANH") (class "Default")
      (node (ref "D32") (pin "1") (pinfunction "1_1") (pintype "passive"))
      (node (ref "R93") (pin "1") (pinfunction "1_1") (pintype "passive"))
      (node (ref "U9") (pin "7") (pinfunction "CANH_7") (pintype "bidirectional"))
    )
    (net (code "11") (name "/CANL") (class "Default")
      (node (ref "D32") (pin "2") (pinfunction "2_2") (pintype "passive"))
      (node (ref "R92") (pin "2") (pinfunction "2_2") (pintype "passive"))
      (node (ref "U9") (pin "6") (pinfunction "CANL_6") (pintype "bidirectional"))
    )
    (net (code "12") (name "/CAN_R") (class "Default")
      (node (ref "U3") (pin "6") (pinfunction "P1.1/UCB0CLK/ACLK/COMP0.1/A1_6") (pintype "bidirectional"))
      (node (ref "U9") (pin "3") (pinfunction "RXD_3") (pintype "output"))
    )
    (net (code "13") (name "/CAN_T") (class "Default")
      (node (ref "U3") (pin "7") (pinfunction "P1.0/UCB0STE/SMCLK/COMP0.0/A0/VEREF+_7") (pintype "bidirectional"))
      (node (ref "U9") (pin "2") (pinfunction "TXD_2") (pintype "input"))
    )
    (net (code "14") (name "/CEN") (class "Default")
      (node (ref "R89") (pin "1") (pinfunction "1_1") (pintype "passive"))
      (node (ref "U3") (pin "12") (pinfunction "P2.7/TB0CLK/XIN_12") (pintype "bidirectional"))
      (node (ref "U5") (pin "4") (pinfunction "C_4") (pintype "passive"))
    )
    (net (code "15") (name "/Charge_Pump") (class "Default")
      (node (ref "U3") (pin "33") (pinfunction "P3.6_33") (pintype "bidirectional"))
    )
    (net (code "16") (name "/Commu_EN") (class "Default")
      (node (ref "U5") (pin "1") (pinfunction "A_1") (pintype "passive"))
    )
    (net (code "17") (name "/EN") (class "Default")
      (node (ref "Q20") (pin "1") (pinfunction "G_1") (pintype "passive"))
      (node (ref "U3") (pin "18") (pinfunction "P4.5/UCB1CLK_18") (pintype "bidirectional"))
    )
    (net (code "18") (name "/F_CON") (class "Default")
      (node (ref "U3") (pin "23") (pinfunction "P4.0/UCA1STE/ISOTXD/ISORXD_23") (pintype "bidirectional"))
    )
    (net (code "19") (name "/LED1") (class "Default")
      (node (ref "D23") (pin "2") (pinfunction "A_2") (pintype "passive"))
      (node (ref "U3") (pin "1") (pinfunction "P3.2_1") (pintype "bidirectional"))
    )
    (net (code "20") (name "/LED2") (class "Default")
      (node (ref "D24") (pin "2") (pinfunction "A_2") (pintype "passive"))
      (node (ref "U3") (pin "2") (pinfunction "P3.1_2") (pintype "bidirectional"))
    )
    (net (code "21") (name "/LED3") (class "Default")
      (node (ref "D25") (pin "2") (pinfunction "A_2") (pintype "passive"))
      (node (ref "U3") (pin "3") (pinfunction "P3.0/MCLK_3") (pintype "bidirectional"))
    )
    (net (code "22") (name "/LED4") (class "Default")
      (node (ref "D26") (pin "2") (pinfunction "A_2") (pintype "passive"))
      (node (ref "U3") (pin "4") (pinfunction "P1.3/UCB0SOMI/UCB0SCL/A3_4") (pintype "bidirectional"))
    )
    (net (code "23") (name "/LED5") (class "Default")
      (node (ref "D27") (pin "2") (pinfunction "A_2") (pintype "passive"))
      (node (ref "U3") (pin "5") (pinfunction "P1.2/UCB0SIMO/UCB0SDA/TB0TRG/A2/VEREF-_5") (pintype "bidirectional"))
    )
    (net (code "24") (name "/PMON") (class "Default")
      (node (ref "U3") (pin "32") (pinfunction "P3.7_32") (pintype "bidirectional"))
    )
    (net (code "25") (name "/PRES") (class "Default")
      (node (ref "U3") (pin "34") (pinfunction "P3.5_34") (pintype "bidirectional"))
    )
    (net (code "26") (name "/Pack_ADC") (class "Default")
      (node (ref "U3") (pin "37") (pinfunction "P5.0/TB2.1/MFM.RX/A8_37") (pintype "bidirectional"))
    )
    (net (code "27") (name "/Pre_discharge") (class "Default")
      (node (ref "U3") (pin "31") (pinfunction "P1.4/UCA0STE/TCK/A4_31") (pintype "bidirectional"))
    )
    (net (code "28") (name "/REG25") (class "Default")
      (node (ref "C37") (pin "1") (pinfunction "1_1") (pintype "passive"))
      (node (ref "RT4") (pin "2") (pinfunction "2_2") (pintype "passive"))
      (node (ref "U4") (pin "7") (pinfunction "REG25_7") (pintype "power_in"))
    )
    (net (code "29") (name "/RXD") (class "Default")
      (node (ref "R88") (pin "1") (pinfunction "1_1") (pintype "passive"))
      (node (ref "U3") (pin "21") (pinfunction "P4.2/UCA1RXD/UCA1SOMI/~{UCA1RXD}_21") (pintype "bidirectional"))
      (node (ref "U7") (pin "4") (pinfunction "C_4") (pintype "passive"))
    )
    (net (code "30") (name "/SBCLK") (class "Default")
      (node (ref "R85") (pin "1") (pinfunction "1_1") (pintype "passive"))
      (node (ref "U3") (pin "8") (pinfunction "TEST/SBWTCK_8") (pintype "input"))
    )
    (net (code "31") (name "/SBIO") (class "Default")
      (node (ref "C38") (pin "1") (pinfunction "1_1") (pintype "passive"))
      (node (ref "R82") (pin "1") (pinfunction "1_1") (pintype "passive"))
      (node (ref "R84") (pin "1") (pinfunction "1_1") (pintype "passive"))
      (node (ref "S2") (pin "1") (pinfunction "1_1") (pintype "passive"))
      (node (ref "U3") (pin "9") (pinfunction "~{RST}/NMI/SBWTDIO_9") (pintype "bidirectional"))
    )
    (net (code "32") (name "/SCL") (class "Default")
      (node (ref "P1") (pin "3") (pinfunction "3_3") (pintype "passive"))
      (node (ref "R83") (pin "2") (pinfunction "2_2") (pintype "passive"))
      (node (ref "U4") (pin "13") (pinfunction "P4/SCL_13") (pintype "input"))
    )
    (net (code "33") (name "/SCL-Gauge") (class "Default")
      (node (ref "P1") (pin "4") (pinfunction "4_4") (pintype "passive"))
      (node (ref "U3") (pin "16") (pinfunction "P4.7/UCB1SOMI/UCB1SCL_16") (pintype "bidirectional"))
    )
    (net (code "34") (name "/SDA") (class "Default")
      (node (ref "P1") (pin "1") (pinfunction "1_1") (pintype "passive"))
      (node (ref "R81") (pin "2") (pinfunction "2_2") (pintype "passive"))
      (node (ref "U4") (pin "14") (pinfunction "P3/SDA_14") (pintype "bidirectional"))
    )
    (net (code "35") (name "/SDA-Gauge") (class "Default")
      (node (ref "P1") (pin "2") (pinfunction "2_2") (pintype "passive"))
      (node (ref "U3") (pin "17") (pinfunction "P4.6/UCB1SIMO/UCB1SDA_17") (pintype "bidirectional"))
    )
    (net (code "36") (name "/SRN") (class "Default")
      (node (ref "U4") (pin "10") (pinfunction "SRN_10") (pintype "input"))
    )
    (net (code "37") (name "/SRP") (class "Default")
      (node (ref "U4") (pin "9") (pinfunction "SRP_9") (pintype "input"))
    )
    (net (code "38") (name "/TXD") (class "Default")
      (node (ref "R86") (pin "2") (pinfunction "2_2") (pintype "passive"))
      (node (ref "U3") (pin "20") (pinfunction "P4.3/UCA1TXD/UCA1SIMO/~{UCA1TXD}_20") (pintype "bidirectional"))
    )
    (net (code "39") (name "/Wake_AFE") (class "Default")
      (node (ref "U3") (pin "35") (pinfunction "P3.4/SMCLK_35") (pintype "bidirectional"))
    )
    (net (code "40") (name "/Wake_Power") (class "Default")
      (node (ref "U3") (pin "24") (pinfunction "P2.3/TB1TRG_24") (pintype "bidirectional"))
    )
    (net (code "41") (name "GND") (class "Default")
      (node (ref "C31") (pin "1") (pinfunction "1_1") (pintype "passive"))
      (node (ref "C32") (pin "2") (pinfunction "2_2") (pintype "passive"))
      (node (ref "C33") (pin "1") (pinfunction "1_1") (pintype "passive"))
      (node (ref "C34") (pin "2") (pinfunction "2_2") (pintype "passive"))
      (node (ref "C35") (pin "2") (pinfunction "2_2") (pintype "passive"))
      (node (ref "C36") (pin "2") (pinfunction "2_2") (pintype "passive"))
      (node (ref "C37") (pin "2") (pinfunction "2_2") (pintype "passive"))
      (node (ref "C38") (pin "2") (pinfunction "2_2") (pintype "passive"))
      (node (ref "C39") (pin "1") (pinfunction "1_1") (pintype "passive"))
      (node (ref "C40") (pin "2") (pinfunction "2_2") (pintype "passive"))
      (node (ref "C42") (pin "2") (pinfunction "2_2") (pintype "passive"))
      (node (ref "C44") (pin "2") (pinfunction "2_2") (pintype "passive"))
      (node (ref "D28") (pin "2") (pinfunction "A_2") (pintype "passive"))
      (node (ref "D29") (pin "2") (pinfunction "A_2") (pintype "passive"))
      (node (ref "P2") (pin "4") (pinfunction "4_4") (pintype "passive"))
      (node (ref "Q17") (pin "2") (pinfunction "S_2") (pintype "passive"))
      (node (ref "Q20") (pin "2") (pinfunction "S_2") (pintype "passive"))
      (node (ref "R73") (pin "1") (pinfunction "1_1") (pintype "passive"))
      (node (ref "R76") (pin "1") (pinfunction "1_1") (pintype "passive"))
      (node (ref "R77") (pin "1") (pinfunction "1_1") (pintype "passive"))
      (node (ref "R78") (pin "1") (pinfunction "1_1") (pintype "passive"))
      (node (ref "R79") (pin "1") (pinfunction "1_1") (pintype "passive"))
      (node (ref "R80") (pin "1") (pinfunction "1_1") (pintype "passive"))
      (node (ref "S2") (pin "2") (pinfunction "2_2") (pintype "passive"))
      (node (ref "U10") (pin "1") (pinfunction "GND_1") (pintype "power_in"))
      (node (ref "U10") (pin "5") (pinfunction "NC_5") (pintype "passive"))
      (node (ref "U2") (pin "1") (pinfunction "GND_1") (pintype "power_in"))
      (node (ref "U2") (pin "5") (pinfunction "NC_5") (pintype "passive"))
      (node (ref "U3") (pin "11") (pinfunction "DVSS_11") (pintype "power_in"))
      (node (ref "U4") (pin "12") (pinfunction "P5/HDQ_12") (pintype "bidirectional"))
      (node (ref "U4") (pin "3") (pinfunction "P1_3") (pintype "output"))
      (node (ref "U4") (pin "8") (pinfunction "VSS_8") (pintype "power_in"))
      (node (ref "U5") (pin "3") (pinfunction "E_3") (pintype "passive"))
      (node (ref "U6") (pin "2") (pinfunction "K_2") (pintype "passive"))
      (node (ref "U7") (pin "3") (pinfunction "E_3") (pintype "passive"))
      (node (ref "U8") (pin "4") (pinfunction "GND_4") (pintype "power_in"))
      (node (ref "U8") (pin "5") (pinfunction "GND_5") (pintype "power_in"))
      (node (ref "U9") (pin "4") (pinfunction "GND1_4") (pintype "power_in"))
    )
    (net (code "42") (name "Net-(C45-Pad2)") (class "Default")
      (node (ref "C45") (pin "2") (pinfunction "2_2") (pintype "passive"))
      (node (ref "R92") (pin "1") (pinfunction "1_1") (pintype "passive"))
      (node (ref "R93") (pin "2") (pinfunction "2_2") (pintype "passive"))
    )
    (net (code "43") (name "Net-(D23-K)") (class "Default")
      (node (ref "D23") (pin "1") (pinfunction "K_1") (pintype "passive"))
      (node (ref "R76") (pin "2") (pinfunction "2_2") (pintype "passive"))
    )
    (net (code "44") (name "Net-(D24-K)") (class "Default")
      (node (ref "D24") (pin "1") (pinfunction "K_1") (pintype "passive"))
      (node (ref "R77") (pin "2") (pinfunction "2_2") (pintype "passive"))
    )
    (net (code "45") (name "Net-(D25-K)") (class "Default")
      (node (ref "D25") (pin "1") (pinfunction "K_1") (pintype "passive"))
      (node (ref "R78") (pin "2") (pinfunction "2_2") (pintype "passive"))
    )
    (net (code "46") (name "Net-(D26-K)") (class "Default")
      (node (ref "D26") (pin "1") (pinfunction "K_1") (pintype "passive"))
      (node (ref "R79") (pin "2") (pinfunction "2_2") (pintype "passive"))
    )
    (net (code "47") (name "Net-(D27-K)") (class "Default")
      (node (ref "D27") (pin "1") (pinfunction "K_1") (pintype "passive"))
      (node (ref "R80") (pin "2") (pinfunction "2_2") (pintype "passive"))
    )
    (net (code "48") (name "Net-(D28-K)") (class "Default")
      (node (ref "D28") (pin "1") (pinfunction "K_1") (pintype "passive"))
      (node (ref "P2") (pin "3") (pinfunction "3_3") (pintype "passive"))
      (node (ref "R84") (pin "2") (pinfunction "2_2") (pintype "passive"))
    )
    (net (code "49") (name "Net-(D29-K)") (class "Default")
      (node (ref "D29") (pin "1") (pinfunction "K_1") (pintype "passive"))
      (node (ref "P2") (pin "2") (pinfunction "2_2") (pintype "passive"))
      (node (ref "R85") (pin "2") (pinfunction "2_2") (pintype "passive"))
    )
    (net (code "50") (name "Net-(D30-A)") (class "Default")
      (node (ref "D30") (pin "2") (pinfunction "A_2") (pintype "passive"))
      (node (ref "T1") (pin "6") (pinfunction "6_6") (pintype "passive"))
    )
    (net (code "51") (name "Net-(D30-K)") (class "Default")
      (node (ref "C46") (pin "1") (pinfunction "1_1") (pintype "passive"))
      (node (ref "D30") (pin "1") (pinfunction "K_1") (pintype "passive"))
      (node (ref "D31") (pin "1") (pinfunction "K_1") (pintype "passive"))
      (node (ref "U12") (pin "2") (pinfunction "IN_2") (pintype "power_in"))
      (node (ref "U12") (pin "4") (pinfunction "NC_4") (pintype "passive"))
    )
    (net (code "52") (name "Net-(D31-A)") (class "Default")
      (node (ref "D31") (pin "2") (pinfunction "A_2") (pintype "passive"))
      (node (ref "T1") (pin "4") (pinfunction "4_4") (pintype "passive"))
    )
    (net (code "53") (name "Net-(Q16-D)") (class "Default")
      (node (ref "Q16") (pin "3") (pinfunction "D_3") (pintype "passive"))
      (node (ref "R71") (pin "1") (pinfunction "1_1") (pintype "passive"))
    )
    (net (code "54") (name "Net-(Q16-G)") (class "Default")
      (node (ref "Q16") (pin "1") (pinfunction "G_1") (pintype "passive"))
      (node (ref "R69") (pin "2") (pinfunction "2_2") (pintype "passive"))
      (node (ref "R70") (pin "1") (pinfunction "1_1") (pintype "passive"))
    )
    (net (code "55") (name "Net-(Q17-D)") (class "Default")
      (node (ref "Q17") (pin "3") (pinfunction "D_3") (pintype "passive"))
      (node (ref "R70") (pin "2") (pinfunction "2_2") (pintype "passive"))
    )
    (net (code "56") (name "Net-(Q17-G)") (class "Default")
      (node (ref "Q17") (pin "1") (pinfunction "G_1") (pintype "passive"))
      (node (ref "U4") (pin "2") (pinfunction "VEN_2") (pintype "output"))
    )
    (net (code "57") (name "Net-(Q18-D)") (class "Default")
      (node (ref "Q18") (pin "3") (pinfunction "D_3") (pintype "passive"))
      (node (ref "R81") (pin "1") (pinfunction "1_1") (pintype "passive"))
      (node (ref "R83") (pin "1") (pinfunction "1_1") (pintype "passive"))
    )
    (net (code "58") (name "Net-(Q18-G)") (class "Default")
      (node (ref "Q18") (pin "1") (pinfunction "G_1") (pintype "passive"))
      (node (ref "U3") (pin "22") (pinfunction "P4.1/UCA1CLK_22") (pintype "bidirectional"))
    )
    (net (code "59") (name "Net-(Q19-D)") (class "Default")
      (node (ref "C40") (pin "1") (pinfunction "1_1") (pintype "passive"))
      (node (ref "C42") (pin "1") (pinfunction "1_1") (pintype "passive"))
      (node (ref "Q19") (pin "3") (pinfunction "D_3") (pintype "passive"))
      (node (ref "T1") (pin "2") (pinfunction "2_2") (pintype "passive"))
      (node (ref "U10") (pin "2") (pinfunction "IN_2") (pintype "power_in"))
      (node (ref "U10") (pin "4") (pinfunction "NC_4") (pintype "passive"))
      (node (ref "U8") (pin "2") (pinfunction "VCC_2") (pintype "power_in"))
    )
    (net (code "60") (name "Net-(Q19-G)") (class "Default")
      (node (ref "Q19") (pin "1") (pinfunction "G_1") (pintype "passive"))
      (node (ref "Q20") (pin "3") (pinfunction "D_3") (pintype "passive"))
      (node (ref "R87") (pin "2") (pinfunction "2_2") (pintype "passive"))
    )
    (net (code "61") (name "Net-(R71-Pad2)") (class "Default")
      (node (ref "R71") (pin "2") (pinfunction "2_2") (pintype "passive"))
      (node (ref "R72") (pin "1") (pinfunction "1_1") (pintype "passive"))
    )
    (net (code "62") (name "Net-(U4-BAT)") (class "Default")
      (node (ref "R72") (pin "2") (pinfunction "2_2") (pintype "passive"))
      (node (ref "R73") (pin "2") (pinfunction "2_2") (pintype "passive"))
      (node (ref "U4") (pin "4") (pinfunction "BAT_4") (pintype "input"))
    )
    (net (code "63") (name "Net-(U4-CE)") (class "Default")
      (node (ref "C36") (pin "1") (pinfunction "1_1") (pintype "passive"))
      (node (ref "R74") (pin "2") (pinfunction "2_2") (pintype "passive"))
      (node (ref "U4") (pin "5") (pinfunction "CE_5") (pintype "input"))
      (node (ref "U4") (pin "6") (pinfunction "REGIN_6") (pintype "power_in"))
    )
    (net (code "64") (name "Net-(U4-P6{slash}TS)") (class "Default")
      (node (ref "RT4") (pin "1") (pinfunction "1_1") (pintype "passive"))
      (node (ref "U4") (pin "11") (pinfunction "P6/TS_11") (pintype "input"))
    )
    (net (code "65") (name "Net-(U6-A)") (class "Default")
      (node (ref "R86") (pin "1") (pinfunction "1_1") (pintype "passive"))
      (node (ref "U6") (pin "1") (pinfunction "A_1") (pintype "passive"))
    )
    (net (code "66") (name "Net-(U7-A)") (class "Default")
      (node (ref "R91") (pin "1") (pinfunction "1_1") (pintype "passive"))
      (node (ref "U7") (pin "1") (pinfunction "A_1") (pintype "passive"))
    )
    (net (code "67") (name "Net-(U8-D1)") (class "Default")
      (node (ref "T1") (pin "3") (pinfunction "3_3") (pintype "passive"))
      (node (ref "U8") (pin "1") (pinfunction "D1_1") (pintype "output"))
    )
    (net (code "68") (name "Net-(U8-D2)") (class "Default")
      (node (ref "T1") (pin "1") (pinfunction "1_1") (pintype "passive"))
      (node (ref "U8") (pin "3") (pinfunction "D2_3") (pintype "output"))
    )
    (net (code "69") (name "Net-(U11-D)") (class "Default")
      (node (ref "R90") (pin "1") (pinfunction "1_1") (pintype "passive"))
      (node (ref "U11") (pin "4") (pinfunction "D_4") (pintype "input"))
      (node (ref "U6") (pin "4") (pinfunction "C_4") (pintype "passive"))
    )
    (net (code "70") (name "Net-(U11-R)") (class "Default")
      (node (ref "R91") (pin "2") (pinfunction "2_2") (pintype "passive"))
      (node (ref "U11") (pin "1") (pinfunction "R_1") (pintype "output"))
    )
    (net (code "71") (name "SGND") (class "Default")
      (node (ref "C41") (pin "2") (pinfunction "2_2") (pintype "passive"))
      (node (ref "C43") (pin "2") (pinfunction "2_2") (pintype "passive"))
      (node (ref "C45") (pin "1") (pinfunction "1_1") (pintype "passive"))
      (node (ref "C46") (pin "2") (pinfunction "2_2") (pintype "passive"))
      (node (ref "C47") (pin "2") (pinfunction "2_2") (pintype "passive"))
      (node (ref "D32") (pin "3") (pinfunction "3_3") (pintype "passive"))
      (node (ref "T1") (pin "5") (pinfunction "5_5") (pintype "passive"))
      (node (ref "U11") (pin "2") (pinfunction "RE_2") (pintype "input"))
      (node (ref "U11") (pin "5") (pinfunction "GND_5") (pintype "power_in"))
      (node (ref "U12") (pin "1") (pinfunction "GND_1") (pintype "power_in"))
      (node (ref "U12") (pin "5") (pinfunction "NC_5") (pintype "passive"))
      (node (ref "U13") (pin "3") (pinfunction "GND_3") (pintype "power_in"))
      (node (ref "U5") (pin "2") (pinfunction "K_2") (pintype "passive"))
      (node (ref "U6") (pin "3") (pinfunction "E_3") (pintype "passive"))
      (node (ref "U7") (pin "2") (pinfunction "K_2") (pintype "passive"))
      (node (ref "U9") (pin "5") (pinfunction "GND2_5") (pintype "power_in"))
    )
    (net (code "72") (name "unconnected-(U3-P1.5{slash}UCA0CLK{slash}TMS{slash}A5-Pad30)") (class "Default")
      (node (ref "U3") (pin "30") (pinfunction "P1.5/UCA0CLK/TMS/A5_30") (pintype "bidirectional"))
    )
    (net (code "73") (name "unconnected-(U3-P1.6{slash}UCA0RXD{slash}UCA0SOMI{slash}TB0.1{slash}TDI{slash}TCLK{slash}A6-Pad29)") (class "Default")
      (node (ref "U3") (pin "29") (pinfunction "P1.6/UCA0RXD/UCA0SOMI/TB0.1/TDI/TCLK/A6_29") (pintype "bidirectional"))
    )
    (net (code "74") (name "unconnected-(U3-P1.7{slash}UCA0TXD{slash}UCA0SIMO{slash}TB0.2{slash}TDO{slash}A7{slash}VREF+-Pad28)") (class "Default")
      (node (ref "U3") (pin "28") (pinfunction "P1.7/UCA0TXD/UCA0SIMO/TB0.2/TDO/A7/VREF+_28") (pintype "bidirectional"))
    )
    (net (code "75") (name "unconnected-(U3-P2.1{slash}TB1.2{slash}COMP1.O-Pad26)") (class "Default")
      (node (ref "U3") (pin "26") (pinfunction "P2.1/TB1.2/COMP1.O_26") (pintype "bidirectional"))
    )
    (net (code "76") (name "unconnected-(U3-P2.4{slash}COMP1.1-Pad15)") (class "Default")
      (node (ref "U3") (pin "15") (pinfunction "P2.4/COMP1.1_15") (pintype "bidirectional"))
    )
    (net (code "77") (name "unconnected-(U3-P2.5{slash}COMP1.0-Pad14)") (class "Default")
      (node (ref "U3") (pin "14") (pinfunction "P2.5/COMP1.0_14") (pintype "bidirectional"))
    )
    (net (code "78") (name "unconnected-(U3-P2.6{slash}MCLK{slash}XOUT-Pad13)") (class "Default")
      (node (ref "U3") (pin "13") (pinfunction "P2.6/MCLK/XOUT_13") (pintype "bidirectional"))
    )
    (net (code "79") (name "unconnected-(U3-P3.3-Pad38)") (class "Default")
      (node (ref "U3") (pin "38") (pinfunction "P3.3_38") (pintype "bidirectional"))
    )
    (net (code "80") (name "unconnected-(U3-P4.4{slash}UCB1STE-Pad19)") (class "Default")
      (node (ref "U3") (pin "19") (pinfunction "P4.4/UCB1STE_19") (pintype "bidirectional"))
    )
    (net (code "81") (name "unconnected-(U3-P5.1{slash}TB2.2{slash}MFM.TX{slash}A9-Pad36)") (class "Default")
      (node (ref "U3") (pin "36") (pinfunction "P5.1/TB2.2/MFM.TX/A9_36") (pintype "bidirectional"))
    )
  )
)
